# PMP20873E1_Power.net
KiCad netlist of a schematic drawn in Altium Designer
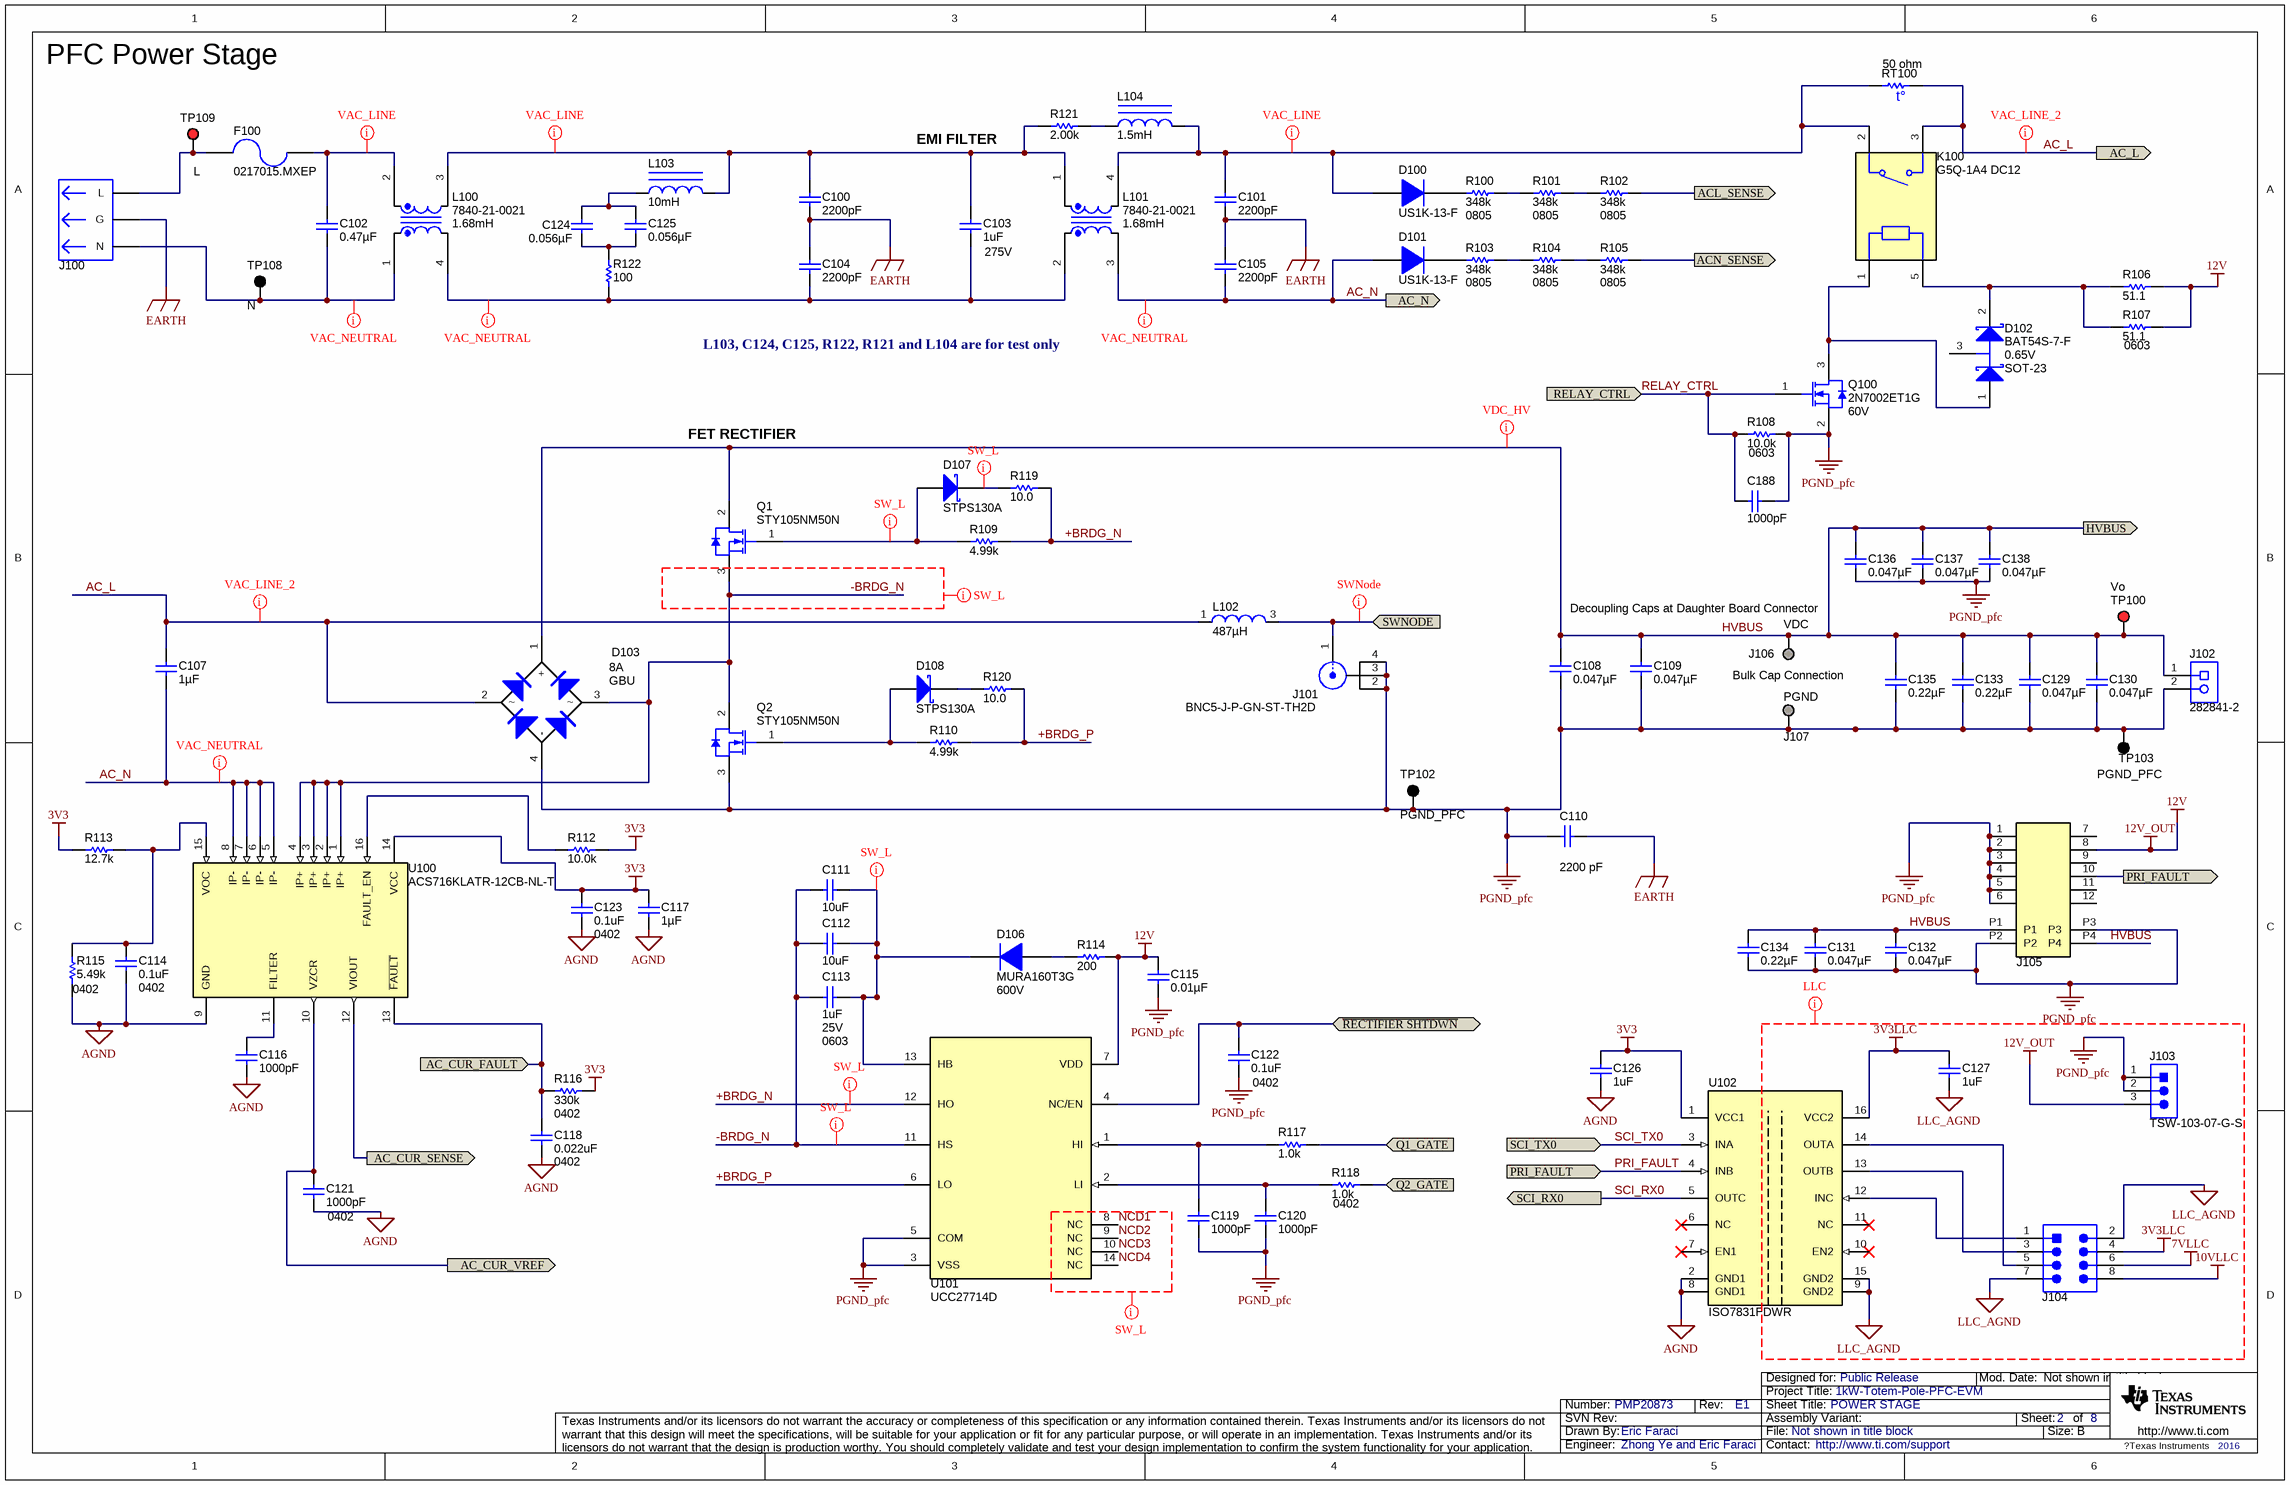
[diagram p0: PMP20873E1_Power.SchDoc]

(export (version "E")
  (design (tool "Eeschema 10.0.6"))
  (components
    (comp (ref "C100")
      (value "DE2E3KY222MA2BM01")
      (footprint "CAPRD500W60D800H850")
      (description "CAP, CERM, 2200pF, 250V, +/-20%, KY, Radial D8x5mm")
      (fields (field (name "VALUEDISPLAYED") "2200pF") (field (name "MANUFACTURER") "MuRata"))
      (libsource (lib "Capacitor_Ceramic") (part "DE2E3KY222MA2BM01"))
    )
    (comp (ref "C101")
      (value "DE2E3KY222MA2BM01")
      (footprint "CAPRD500W60D800H850")
      (description "CAP, CERM, 2200pF, 250V, +/-20%, KY, Radial D8x5mm")
      (fields (field (name "VALUEDISPLAYED") "2200pF") (field (name "MANUFACTURER") "MuRata"))
      (libsource (lib "Capacitor_Ceramic") (part "DE2E3KY222MA2BM01"))
    )
    (comp (ref "C102")
      (value "ECQ-U2A474ML")
      (footprint "CAPRR2250W80L2550T850H1750")
      (description "CAP, Film, 0.47 µF, 275 V, +/- 20%, TH")
      (fields (field (name "VALUEDISPLAYED") "0.47µF") (field (name "MANUFACTURER") "Panasonic"))
      (libsource (lib "Capacitor_Other") (part "ECQ-U2A474ML"))
    )
    (comp (ref "C103")
      (value "R46KN-4100--P1 M")
      (footprint "CAPRR2250W80L2550T850H1750")
      (description "CAP, Film, 1uF, 275V, +/-20%, TH")
      (fields
        (field (name "MANUFACTURER") "Panasonic")
        (field (name "VALUE2") "275V")
        (field (name "ALTERNATE PARTNUMBER") "R46KN410000P1M")
        (field (name "VALUEDISPLAYED") "1uF")
      )
      (libsource (lib "Capacitor_Other") (part "ECQ-U2A474ML"))
    )
    (comp (ref "C104")
      (value "DE2E3KY222MA2BM01")
      (footprint "CAPRD500W60D800H850")
      (description "CAP, CERM, 2200pF, 250V, +/-20%, KY, Radial D8x5mm")
      (fields (field (name "VALUEDISPLAYED") "2200pF") (field (name "MANUFACTURER") "MuRata"))
      (libsource (lib "Capacitor_Ceramic") (part "DE2E3KY222MA2BM01"))
    )
    (comp (ref "C105")
      (value "DE2E3KY222MA2BM01")
      (footprint "CAPRD500W60D800H850")
      (description "CAP, CERM, 2200pF, 250V, +/-20%, KY, Radial D8x5mm")
      (fields (field (name "VALUEDISPLAYED") "2200pF") (field (name "MANUFACTURER") "MuRata"))
      (libsource (lib "Capacitor_Ceramic") (part "DE2E3KY222MA2BM01"))
    )
    (comp (ref "C107")
      (value "450MPK105J")
      (footprint "MPK_1800x950")
      (description "CAP, Film, 1 µF, 450 V, +/- 5%, TH")
      (fields (field (name "VALUEDISPLAYED") "1µF") (field (name "MANUFACTURER") "Rubycon"))
      (libsource (lib "Capacitor_Other") (part "450MPK105J"))
    )
    (comp (ref "C108")
      (value "GRM32DR72J473KW01L")
      (footprint "1210")
      (description "CAP, CERM, 0.047 µF, 630 V, +/- 10%, X7R, 1210")
      (fields (field (name "VALUEDISPLAYED") "0.047µF") (field (name "MANUFACTURER") "MuRata"))
      (libsource (lib "Capacitor_Ceramic") (part "GRM32DR72J473KW01L"))
    )
    (comp (ref "C109")
      (value "GRM32DR72J473KW01L")
      (footprint "1210")
      (description "CAP, CERM, 0.047 µF, 630 V, +/- 10%, X7R, 1210")
      (fields (field (name "VALUEDISPLAYED") "0.047µF") (field (name "MANUFACTURER") "MuRata"))
      (libsource (lib "Capacitor_Ceramic") (part "GRM32DR72J473KW01L"))
    )
    (comp (ref "C110")
      (value "2200 pF")
      (footprint "CAPRD1000W60D900H1200")
      (description "CAP, CERM, 2200pF, 250V, +/-20%, E, Cap, 7x12x9 mm TH")
      (fields (field (name "MANUFACTURER") "Kemet") (field (name "PARTNUMBER") "C921U222MYWDBA7317"))
      (libsource (lib "Capacitor_Ceramic") (part "DE1E3KX222MA4BL01"))
    )
    (comp (ref "C111")
      (value "0805YD106MAT2A")
      (footprint "0805_HV")
      (description "CAP, CERM, 10uF, 16V, +/-20%, X5R, 0805")
      (fields (field (name "VALUEDISPLAYED") "10uF") (field (name "MANUFACTURER") "AVX"))
      (libsource (lib "Capacitor_Ceramic") (part "0805YD106MAT2A"))
    )
    (comp (ref "C112")
      (value "0805YD106MAT2A")
      (footprint "0805_HV")
      (description "CAP, CERM, 10uF, 16V, +/-20%, X5R, 0805")
      (fields (field (name "VALUEDISPLAYED") "10uF") (field (name "MANUFACTURER") "AVX"))
      (libsource (lib "Capacitor_Ceramic") (part "0805YD106MAT2A"))
    )
    (comp (ref "C113")
      (value "C1608X7R1E105K080AB")
      (footprint "0603")
      (description "CAP, CERM, 1uF, 25V, +/-10%, X7R, 0603")
      (fields
        (field (name "VALUEDISPLAYED") "1uF")
        (field (name "MANUFACTURER") "TDK")
        (field (name "VALUE2") "25V")
        (field (name "CAP_CASE") "0603")
      )
      (libsource (lib "Capacitor_Ceramic") (part "C1608X7R1E105K080AB"))
    )
    (comp (ref "C114")
      (value "GRM155R70J104KA01D")
      (footprint "0402")
      (description "CAP, CERM, 0.1uF, 6.3V, +/-10%, X7R, 0402")
      (fields
        (field (name "VALUEDISPLAYED") "0.1uF")
        (field (name "MANUFACTURER") "MuRata")
        (field (name "CAP_CASE") "0402")
      )
      (libsource (lib "Capacitor_Ceramic") (part "GRM155R70J104KA01D"))
    )
    (comp (ref "C115")
      (value "C0603X103K5RACTU")
      (footprint "0603")
      (description "CAP, CERM, 0.01uF, 50V, +/-10%, X7R, 0603")
      (fields (field (name "VALUEDISPLAYED") "0.01µF") (field (name "MANUFACTURER") "Kemet"))
      (libsource (lib "Capacitor_Ceramic") (part "C0603X103K5RACTU"))
    )
    (comp (ref "C116")
      (value "C1608X7R1H102K")
      (footprint "0603")
      (description "CAP, CERM, 1000pF, 50V, +/-10%, X7R, 0603")
      (fields (field (name "VALUEDISPLAYED") "1000pF") (field (name "MANUFACTURER") "TDK"))
      (libsource (lib "Capacitor_Ceramic") (part "C1608X7R1H102K"))
    )
    (comp (ref "C117")
      (value "GRM185R60J105KE26D")
      (footprint "0603")
      (description "CAP, CERM, 1uF, 6.3V, +/-10%, X5R, 0603")
      (fields (field (name "VALUEDISPLAYED") "1µF") (field (name "MANUFACTURER") "MuRata"))
      (libsource (lib "Capacitor_Ceramic") (part "GRM185R60J105KE26D"))
    )
    (comp (ref "C118")
      (value "GRM155R70J223KA01D")
      (footprint "0402")
      (description "CAP, CERM, 0.022uF, 6.3V, +/-10%, X7R, 0402")
      (fields
        (field (name "VALUEDISPLAYED") "0.022uF")
        (field (name "MANUFACTURER") "MuRata")
        (field (name "PACKAGEREFERENCE") "0402")
      )
      (libsource (lib "Capacitor_Ceramic") (part "GRM155R70J223KA01D"))
    )
    (comp (ref "C119")
      (value "C1005X7R1H102K")
      (footprint "0402")
      (description "CAP, CERM, 1000pF, 50V, +/-10%, X7R, 0402")
      (fields (field (name "VALUEDISPLAYED") "1000pF") (field (name "MANUFACTURER") "TDK"))
      (libsource (lib "Capacitor_Ceramic") (part "C1005X7R1H102K"))
    )
    (comp (ref "C120")
      (value "GRM155R60J102KA01D")
      (footprint "0402")
      (description "CAP, CERM, 1000pF, 6.3V, +/-10%, X5R, 0402")
      (fields (field (name "VALUEDISPLAYED") "1000pF") (field (name "MANUFACTURER") "MuRata"))
      (libsource (lib "Capacitor_Ceramic") (part "GRM155R60J102KA01D"))
    )
    (comp (ref "C121")
      (value "GRM155R60J102KA01D")
      (footprint "0402")
      (description "CAP, CERM, 1000pF, 6.3V, +/-10%, X5R, 0402")
      (fields
        (field (name "VALUEDISPLAYED") "1000pF")
        (field (name "MANUFACTURER") "MuRata")
        (field (name "PACKAGEREFERENCE") "0402")
      )
      (libsource (lib "Capacitor_Ceramic") (part "GRM155R60J102KA01D"))
    )
    (comp (ref "C122")
      (value "GRM155R70J104KA01D")
      (footprint "0402")
      (description "CAP, CERM, 0.1uF, 6.3V, +/-10%, X7R, 0402")
      (fields
        (field (name "VALUEDISPLAYED") "0.1uF")
        (field (name "MANUFACTURER") "MuRata")
        (field (name "PACKAGEREFERENCE") "0402")
      )
      (libsource (lib "Capacitor_Ceramic") (part "GRM155R70J104KA01D"))
    )
    (comp (ref "C123")
      (value "GRM155R70J104KA01D")
      (footprint "0402")
      (description "CAP, CERM, 0.1uF, 6.3V, +/-10%, X7R, 0402")
      (fields
        (field (name "VALUEDISPLAYED") "0.1uF")
        (field (name "MANUFACTURER") "MuRata")
        (field (name "CAP_CASE") "0402")
      )
      (libsource (lib "Capacitor_Ceramic") (part "GRM155R70J104KA01D"))
    )
    (comp (ref "C124")
      (value "GA355XR7GB563KW06L")
      (footprint "2220_330_N")
      (description "CAP, CERM, 0.056 µF, 250 V, +/- 10%, X7R, 2220")
      (fields (field (name "VALUEDISPLAYED") "0.056µF") (field (name "MANUFACTURER") "MuRata"))
      (libsource (lib "Capacitor_Ceramic") (part "GA355XR7GB563KW06L"))
    )
    (comp (ref "C125")
      (value "GA355XR7GB563KW06L")
      (footprint "2220_330_N")
      (description "CAP, CERM, 0.056 µF, 250 V, +/- 10%, X7R, 2220")
      (fields (field (name "VALUEDISPLAYED") "0.056µF") (field (name "MANUFACTURER") "MuRata"))
      (libsource (lib "Capacitor_Ceramic") (part "GA355XR7GB563KW06L"))
    )
    (comp (ref "C126")
      (value "C1608X7R1E105K080AB")
      (footprint "0603")
      (description "CAP, CERM, 1uF, 25V, +/-10%, X7R, 0603")
      (fields (field (name "VALUEDISPLAYED") "1uF") (field (name "MANUFACTURER") "TDK"))
      (libsource (lib "Capacitor_Ceramic") (part "C1608X7R1E105K080AB"))
    )
    (comp (ref "C127")
      (value "C1608X7R1E105K080AB")
      (footprint "0603")
      (description "CAP, CERM, 1uF, 25V, +/-10%, X7R, 0603")
      (fields (field (name "VALUEDISPLAYED") "1uF") (field (name "MANUFACTURER") "TDK"))
      (libsource (lib "Capacitor_Ceramic") (part "C1608X7R1E105K080AB"))
    )
    (comp (ref "C129")
      (value "GRM32DR72J473KW01L")
      (footprint "1210")
      (description "CAP, CERM, 0.047 µF, 630 V, +/- 10%, X7R, 1210")
      (fields (field (name "VALUEDISPLAYED") "0.047µF") (field (name "MANUFACTURER") "MuRata"))
      (libsource (lib "Capacitor_Ceramic") (part "GRM32DR72J473KW01L"))
    )
    (comp (ref "C130")
      (value "GRM32DR72J473KW01L")
      (footprint "1210")
      (description "CAP, CERM, 0.047 µF, 630 V, +/- 10%, X7R, 1210")
      (fields (field (name "VALUEDISPLAYED") "0.047µF") (field (name "MANUFACTURER") "MuRata"))
      (libsource (lib "Capacitor_Ceramic") (part "GRM32DR72J473KW01L"))
    )
    (comp (ref "C131")
      (value "GRM32DR72J473KW01L")
      (footprint "1210")
      (description "CAP, CERM, 0.047 µF, 630 V, +/- 10%, X7R, 1210")
      (fields (field (name "VALUEDISPLAYED") "0.047µF") (field (name "MANUFACTURER") "MuRata"))
      (libsource (lib "Capacitor_Ceramic") (part "GRM32DR72J473KW01L"))
    )
    (comp (ref "C132")
      (value "GRM32DR72J473KW01L")
      (footprint "1210")
      (description "CAP, CERM, 0.047 µF, 630 V, +/- 10%, X7R, 1210")
      (fields (field (name "VALUEDISPLAYED") "0.047µF") (field (name "MANUFACTURER") "MuRata"))
      (libsource (lib "Capacitor_Ceramic") (part "GRM32DR72J473KW01L"))
    )
    (comp (ref "C133")
      (value "GRM55DR72J224KW01L")
      (footprint "2220")
      (description "CAP, CERM, 0.22 µF, 630 V, +/- 10%, X7R, 2220")
      (fields (field (name "VALUEDISPLAYED") "0.22µF") (field (name "MANUFACTURER") "MuRata"))
      (libsource (lib "Capacitor_Ceramic") (part "GRM55DR72J224KW01L"))
    )
    (comp (ref "C134")
      (value "GRM55DR72J224KW01L")
      (footprint "2220")
      (description "CAP, CERM, 0.22 µF, 630 V, +/- 10%, X7R, 2220")
      (fields (field (name "VALUEDISPLAYED") "0.22µF") (field (name "MANUFACTURER") "MuRata"))
      (libsource (lib "Capacitor_Ceramic") (part "GRM55DR72J224KW01L"))
    )
    (comp (ref "C135")
      (value "GRM55DR72J224KW01L")
      (footprint "2220")
      (description "CAP, CERM, 0.22 µF, 630 V, +/- 10%, X7R, 2220")
      (fields (field (name "VALUEDISPLAYED") "0.22µF") (field (name "MANUFACTURER") "MuRata"))
      (libsource (lib "Capacitor_Ceramic") (part "GRM55DR72J224KW01L"))
    )
    (comp (ref "C136")
      (value "GRM32DR72J473KW01L")
      (footprint "1210")
      (description "CAP, CERM, 0.047 µF, 630 V, +/- 10%, X7R, 1210")
      (fields (field (name "VALUEDISPLAYED") "0.047µF") (field (name "MANUFACTURER") "MuRata"))
      (libsource (lib "Capacitor_Ceramic") (part "GRM32DR72J473KW01L"))
    )
    (comp (ref "C137")
      (value "GRM32DR72J473KW01L")
      (footprint "1210")
      (description "CAP, CERM, 0.047 µF, 630 V, +/- 10%, X7R, 1210")
      (fields (field (name "VALUEDISPLAYED") "0.047µF") (field (name "MANUFACTURER") "MuRata"))
      (libsource (lib "Capacitor_Ceramic") (part "GRM32DR72J473KW01L"))
    )
    (comp (ref "C138")
      (value "GRM32DR72J473KW01L")
      (footprint "1210")
      (description "CAP, CERM, 0.047 µF, 630 V, +/- 10%, X7R, 1210")
      (fields (field (name "VALUEDISPLAYED") "0.047µF") (field (name "MANUFACTURER") "MuRata"))
      (libsource (lib "Capacitor_Ceramic") (part "GRM32DR72J473KW01L"))
    )
    (comp (ref "C188")
      (value "GRM188R71C102KA01D")
      (footprint "0603")
      (description "CAP, CERM, 1000pF, 16V, +/-10%, X7R, 0603")
      (fields (field (name "VALUEDISPLAYED") "1000pF") (field (name "MANUFACTURER") "MuRata"))
      (libsource (lib "Capacitor_Ceramic") (part "GRM188R71C102KA01D"))
    )
    (comp (ref "D100")
      (value "US1K-13-F")
      (footprint "SMA")
      (description "Diode, Fast Rectifier, 800 V, 1 A, SMA")
      (fields (field (name "MANUFACTURER") "Diodes Inc."))
      (libsource (lib "Diode") (part "US1K-13-F"))
    )
    (comp (ref "D101")
      (value "US1K-13-F")
      (footprint "SMA")
      (description "Diode, Fast Rectifier, 800 V, 1 A, SMA")
      (fields (field (name "MANUFACTURER") "Diodes Inc."))
      (libsource (lib "Diode") (part "US1K-13-F"))
    )
    (comp (ref "D102")
      (value "BAT54S-7-F")
      (footprint "SOT-23")
      (description "Diode, Schottky, 30V, 0.2A, SOT-23")
      (fields
        (field (name "MANUFACTURER") "Diodes Inc.")
        (field (name "ALTIUM_VALUE") "0.65V")
        (field (name "PACKAGEREFERENCE") "SOT-23")
      )
      (libsource (lib "Diode") (part "BAT54S-7-F"))
    )
    (comp (ref "D103")
      (value "GBU8J-BP")
      (footprint "GBU")
      (description "Diode, Switching-Bridge, 420V, 8A, TH")
      (fields
        (field (name "MANUFACTURER") "Micro Commercial Components")
        (field (name "PACKAGEREFERENCE") "GBU")
        (field (name "VALUE1") "8A")
      )
      (libsource (lib "Diode") (part "GBU8J-BP"))
    )
    (comp (ref "D106")
      (value "MURA160T3G")
      (footprint "SMA")
      (description "Diode, Ultrafast, 600V, 1A, SMA")
      (fields (field (name "ALTIUM_VALUE") "600V") (field (name "MANUFACTURER") "ON Semiconductor"))
      (libsource (lib "Diode") (part "MURA160T3G"))
    )
    (comp (ref "D107")
      (value "STPS130A")
      (footprint "SMA")
      (description "Diode, Schottky, 30 V, 1 A, SMA")
      (fields (field (name "MANUFACTURER") "STMicroelectronics"))
      (libsource (lib "Diode") (part "STPS130A"))
    )
    (comp (ref "D108")
      (value "STPS130A")
      (footprint "SMA")
      (description "Diode, Schottky, 30 V, 1 A, SMA")
      (fields (field (name "MANUFACTURER") "STMicroelectronics"))
      (libsource (lib "Diode") (part "STPS130A"))
    )
    (comp (ref "F100")
      (value "0217015.MXEP")
      (footprint "Fuse_217_015_Verical")
      (description "Fuse, 15 A, 250 V, TH")
      (fields (field (name "MANUFACTURER") "Littelfuse"))
      (libsource (lib "Fuse") (part "0217015.MXEP"))
    )
    (comp (ref "J100")
      (value "703W-00/54")
      (footprint "CONN_QUALTEK-703W-0054")
      (description "AC Receptacle, 10A 250VAC")
      (fields (field (name "MANUFACTURER") "Qualtek Electronics Corporation"))
      (libsource (lib "Connectors_Other") (part "703W-00/54"))
    )
    (comp (ref "J101")
      (value "BNC5-J-P-GN-ST-TH2D")
      (footprint "Samtec_BNC5-J-P-GN-ST-TH2D")
      (description "50 OHM BNC ELEVATED STRAIGHT JACK, TH")
      (fields (field (name "MANUFACTURER") "Samtec"))
      (libsource (lib "Connectors_Samtec") (part "BNC5-J-P-GN-ST-TH2D"))
    )
    (comp (ref "J102")
      (value "282841-2")
      (footprint "TEC_282841-2")
      (description "Terminal Block, 2x1, 5.08mm, TH")
      (fields (field (name "MANUFACTURER") "TE Connectivity"))
      (libsource (lib "Connectors_TE_Connectivity") (part "282841-2"))
    )
    (comp (ref "J103")
      (value "TSW-103-07-G-S")
      (footprint "TSW-103-07-G-S")
      (description "Header, 100mil, 3x1, Gold, TH")
      (fields (field (name "MANUFACTURER") "Samtec"))
      (libsource (lib "Connectors_Samtec") (part "TSW-103-07-G-S"))
    )
    (comp (ref "J104")
      (value "TSW-104-07-G-D")
      (footprint "TSW-104-07-G-D")
      (description "Header, 100mil, 4x2, Gold, TH")
      (fields (field (name "MANUFACTURER") "Samtec"))
      (libsource (lib "Connectors_Samtec") (part "TSW-104-07-G-D"))
    )
    (comp (ref "J105")
      (value "PESC-02-12-02-01-L-RA-LC")
      (footprint "Samtec_PESC-02-12-02-01-x-RA-LC")
      (description "Signal Power Combo Socket Strip, 4x3, 4 Power Group, R/A, Gold, TH")
      (fields (field (name "MANUFACTURER") "Samtec"))
      (libsource (lib "Connectors_Samtec") (part "PESC-02-12-02-01-L-RA-LC"))
    )
    (comp (ref "J106")
      (value "VDC")
      (footprint "Mill-Max_0312-0-15-15-34-27-10-0")
      (description "Pin Receptacle, .032-.046\" .075\" Dia, Gold, TH")
      (fields (field (name "PARTNUMBER") "0312-0-15-15-34-27-10-0") (field (name "MANUFACTURER") "Mill-Max"))
      (libsource (lib "Connectors_Mill_Max") (part "0312-0-15-15-34-27-10-0"))
    )
    (comp (ref "J107")
      (value "PGND")
      (footprint "Mill-Max_0312-0-15-15-34-27-10-0")
      (description "Pin Receptacle, .032-.046\" .075\" Dia, Gold, TH")
      (fields (field (name "PARTNUMBER") "0312-0-15-15-34-27-10-0") (field (name "MANUFACTURER") "Mill-Max"))
      (libsource (lib "Connectors_Mill_Max") (part "0312-0-15-15-34-27-10-0"))
    )
    (comp (ref "K100")
      (value "G5Q-1A4 DC12")
      (footprint "Relay_G5Q-1A4")
      (description "Relay, SPST-NO (1 Form A), 10 A, 12 VDC, TH")
      (fields (field (name "MANUFACTURER") "Omron Electronic Components"))
      (libsource (lib "Relays") (part "G5Q-1A4 DC12"))
    )
    (comp (ref "L100")
      (value "7840-21-0021")
      (footprint "7840-21-0021")
      (description "Coupled inductor, 1.68 mH,  A,  ohm, TH")
      (fields (field (name "VALUEDISPLAYED") "1.68mH") (field (name "MANUFACTURER") "Nova Magnetics"))
      (libsource (lib "") (part "7840-21-0021_1"))
    )
    (comp (ref "L101")
      (value "7840-21-0021")
      (footprint "7840-21-0021")
      (description "Coupled inductor, 1.68 mH,  A,  ohm, TH")
      (fields (field (name "VALUEDISPLAYED") "1.68mH") (field (name "MANUFACTURER") "Nova Magnetics"))
      (libsource (lib "Coupled_Inductors") (part "7840-21-0021"))
    )
    (comp (ref "L102")
      (value "G164005LF")
      (footprint "IND_7840-09-0014")
      (description "Inductor, Toroid, Ferrite, 481 µH, 0.057 ohm, TH")
      (fields (field (name "VALUEDISPLAYED") "487µH") (field (name "MANUFACTURER") "GCI technologies"))
      (libsource (lib "Inductor_Other") (part "7840-09-0014"))
    )
    (comp (ref "L103")
      (value "ASPI-0403S-103M-T")
      (footprint "ASPI-0403S")
      (description "Inductor, Wirewound, 10 mH, 0.02 A, 32.8 ohm, SMD")
      (fields (field (name "VALUEDISPLAYED") "10mH") (field (name "MANUFACTURER") "Abracon Corporation"))
      (libsource (lib "Inductor_Other") (part "ASPI-0403S-103M-T"))
    )
    (comp (ref "L104")
      (value "LQH43MN152K03L")
      (footprint "LQH43M")
      (description "Inductor, Wirewound, Ferrite, 1.5 mH, 0.04 A, 37 ohm, SMD")
      (fields (field (name "VALUEDISPLAYED") "1.5mH") (field (name "MANUFACTURER") "MuRata"))
      (libsource (lib "Inductor_MuRata") (part "LQH43MN152K03L"))
    )
    (comp (ref "Q1")
      (value "STY105NM50N")
      (footprint "TO-247")
      (description "MOSFET, N-CH, 500 V, 110 A, TO-247")
      (fields (field (name "MANUFACTURER") "STMicroelectronics"))
      (libsource (lib "FETs") (part "STY105NM50N"))
    )
    (comp (ref "Q2")
      (value "STY105NM50N")
      (footprint "TO-247")
      (description "MOSFET, N-CH, 500 V, 110 A, TO-247")
      (fields (field (name "MANUFACTURER") "STMicroelectronics"))
      (libsource (lib "FETs") (part "STY105NM50N"))
    )
    (comp (ref "Q100")
      (value "2N7002ET1G")
      (footprint "SOT-23")
      (description "MOSFET, N-CH, 60V, 0.26A, SOT-23")
      (fields (field (name "MANUFACTURER") "ON Semiconductor") (field (name "ALTIUM_VALUE") "60V"))
      (libsource (lib "FETs") (part "2N7002ET1G"))
    )
    (comp (ref "R100")
      (value "348k")
      (footprint "0805_HV")
      (description "RES, 348k ohm, 0.1%, 0.125W, 0805")
      (fields
        (field (name "PARTNUMBER") "RT0805BRD07348KL")
        (field (name "MANUFACTURER") "Yageo America")
        (field (name "PACKAGEREFERENCE") "0805")
      )
      (libsource (lib "Resistor_0805") (part "RT0805BRD07348KL"))
    )
    (comp (ref "R101")
      (value "348k")
      (footprint "0805_HV")
      (description "RES, 348k ohm, 0.1%, 0.125W, 0805")
      (fields
        (field (name "PARTNUMBER") "RT0805BRD07348KL")
        (field (name "MANUFACTURER") "Yageo America")
        (field (name "PACKAGEREFERENCE") "0805")
      )
      (libsource (lib "Resistor_0805") (part "RT0805BRD07348KL"))
    )
    (comp (ref "R102")
      (value "348k")
      (footprint "0805_HV")
      (description "RES, 348k ohm, 0.1%, 0.125W, 0805")
      (fields
        (field (name "PARTNUMBER") "RT0805BRD07348KL")
        (field (name "MANUFACTURER") "Yageo America")
        (field (name "PACKAGEREFERENCE") "0805")
      )
      (libsource (lib "Resistor_0805") (part "RT0805BRD07348KL"))
    )
    (comp (ref "R103")
      (value "348k")
      (footprint "0805_HV")
      (description "RES, 348k ohm, 0.1%, 0.125W, 0805")
      (fields
        (field (name "PARTNUMBER") "RT0805BRD07348KL")
        (field (name "MANUFACTURER") "Yageo America")
        (field (name "PACKAGEREFERENCE") "0805")
      )
      (libsource (lib "Resistor_0805") (part "RT0805BRD07348KL"))
    )
    (comp (ref "R104")
      (value "348k")
      (footprint "0805_HV")
      (description "RES, 348k ohm, 0.1%, 0.125W, 0805")
      (fields
        (field (name "PARTNUMBER") "RT0805BRD07348KL")
        (field (name "MANUFACTURER") "Yageo America")
        (field (name "PACKAGEREFERENCE") "0805")
      )
      (libsource (lib "Resistor_0805") (part "RT0805BRD07348KL"))
    )
    (comp (ref "R105")
      (value "348k")
      (footprint "0805_HV")
      (description "RES, 348k ohm, 0.1%, 0.125W, 0805")
      (fields
        (field (name "PARTNUMBER") "RT0805BRD07348KL")
        (field (name "MANUFACTURER") "Yageo America")
        (field (name "PACKAGEREFERENCE") "0805")
      )
      (libsource (lib "Resistor_0805") (part "RT0805BRD07348KL"))
    )
    (comp (ref "R106")
      (value "51.1")
      (footprint "0603")
      (description "RES, 51.1 ohm, 1%, 0.1W, 0603")
      (fields (field (name "PARTNUMBER") "CRCW060351R1FKEA") (field (name "MANUFACTURER") "Vishay-Dale"))
      (libsource (lib "Resistor_0603") (part "CRCW060351R1FKEA"))
    )
    (comp (ref "R107")
      (value "51.1")
      (footprint "0603")
      (description "RES, 51.1 ohm, 1%, 0.1W, 0603")
      (fields
        (field (name "PARTNUMBER") "CRCW060351R1FKEA")
        (field (name "MANUFACTURER") "Vishay-Dale")
        (field (name "PACKAGEREFERENCE") "0603")
      )
      (libsource (lib "Resistor_0603") (part "CRCW060351R1FKEA"))
    )
    (comp (ref "R108")
      (value "10.0k")
      (footprint "0603")
      (description "RES, 10.0k ohm, 1%, 0.1W, 0603")
      (fields
        (field (name "PARTNUMBER") "RC0603FR-0710KL")
        (field (name "MANUFACTURER") "Yageo America")
        (field (name "PACKAGEREFERENCE") "0603")
      )
      (libsource (lib "Resistor_0603") (part "RC0603FR-0710KL"))
    )
    (comp (ref "R109")
      (value "ERJ-6ENF4991V")
      (footprint "0805_HV")
      (description "RES, 4.99 k, 1%, 0.125 W, 0805")
      (fields (field (name "VALUEDISPLAYED") "4.99k") (field (name "MANUFACTURER") "Panasonic"))
      (libsource (lib "Resistor_0805") (part "ERJ-6ENF4991V"))
    )
    (comp (ref "R110")
      (value "ERJ-6ENF4991V")
      (footprint "0805_HV")
      (description "RES, 4.99 k, 1%, 0.125 W, 0805")
      (fields (field (name "VALUEDISPLAYED") "4.99k") (field (name "MANUFACTURER") "Panasonic"))
      (libsource (lib "Resistor_0805") (part "ERJ-6ENF4991V"))
    )
    (comp (ref "R112")
      (value "10.0k")
      (footprint "0402")
      (description "RES, 10.0k ohm, 1%, 0.063W, 0402")
      (fields (field (name "PARTNUMBER") "CRCW040210K0FKED") (field (name "MANUFACTURER") "Vishay-Dale"))
      (libsource (lib "Resistor_0402") (part "CRCW040210K0FKED"))
    )
    (comp (ref "R113")
      (value "12.7k")
      (footprint "0402")
      (description "RES, 12.7k ohm, 1%, 0.063W, 0402")
      (fields (field (name "PARTNUMBER") "CRCW040212K7FKED") (field (name "MANUFACTURER") "Vishay-Dale"))
      (libsource (lib "Resistor_0402") (part "CRCW040212K7FKED"))
    )
    (comp (ref "R114")
      (value "200")
      (footprint "0603")
      (description "RES, 200 ohm, 1%, 0.1W, 0603")
      (fields (field (name "PARTNUMBER") "CRCW0603200RFKEA") (field (name "MANUFACTURER") "Vishay-Dale"))
      (libsource (lib "Resistor_0603") (part "CRCW0603200RFKEA"))
    )
    (comp (ref "R115")
      (value "5.49k")
      (footprint "0402")
      (description "RES, 5.49k ohm, 1%, 0.063W, 0402")
      (fields
        (field (name "PARTNUMBER") "CRCW04025K49FKED")
        (field (name "MANUFACTURER") "Vishay-Dale")
        (field (name "PACKAGEREFERENCE") "0402")
      )
      (libsource (lib "Resistor_0402") (part "CRCW04025K49FKED"))
    )
    (comp (ref "R116")
      (value "330k")
      (footprint "0402")
      (description "RES, 330k ohm, 5%, 0.063W, 0402")
      (fields
        (field (name "PARTNUMBER") "CRCW0402330KJNED")
        (field (name "MANUFACTURER") "Vishay-Dale")
        (field (name "PACKAGEREFERENCE") "0402")
      )
      (libsource (lib "Resistor_0402") (part "CRCW0402330KJNED"))
    )
    (comp (ref "R117")
      (value "1.0k")
      (footprint "0402")
      (description "RES, 1.0k ohm, 5%, 0.063W, 0402")
      (fields (field (name "PARTNUMBER") "CRCW04021K00JNED") (field (name "MANUFACTURER") "Vishay-Dale"))
      (libsource (lib "Resistor_0402") (part "CRCW04021K00JNED"))
    )
    (comp (ref "R118")
      (value "1.0k")
      (footprint "0402")
      (description "RES, 1.0k ohm, 5%, 0.063W, 0402")
      (fields
        (field (name "PARTNUMBER") "CRCW04021K00JNED")
        (field (name "MANUFACTURER") "Vishay-Dale")
        (field (name "PACKAGEREFERENCE") "0402")
      )
      (libsource (lib "Resistor_0402") (part "CRCW04021K00JNED"))
    )
    (comp (ref "R119")
      (value "CRCW080510R0FKEA")
      (footprint "0805_HV")
      (description "RES, 10.0, 1%, 0.125 W, 0805")
      (fields (field (name "VALUEDISPLAYED") "10.0") (field (name "MANUFACTURER") "Vishay-Dale"))
      (libsource (lib "Resistor_0805") (part "CRCW080510R0FKEA"))
    )
    (comp (ref "R120")
      (value "CRCW080510R0FKEA")
      (footprint "0805_HV")
      (description "RES, 10.0, 1%, 0.125 W, 0805")
      (fields (field (name "VALUEDISPLAYED") "10.0") (field (name "MANUFACTURER") "Vishay-Dale"))
      (libsource (lib "Resistor_0805") (part "CRCW080510R0FKEA"))
    )
    (comp (ref "R121")
      (value "CRCW12062K00FKEA")
      (footprint "1206")
      (description "RES, 2.00 k, 1%, 0.25 W, 1206")
      (fields (field (name "VALUEDISPLAYED") "2.00k") (field (name "MANUFACTURER") "Vishay-Dale"))
      (libsource (lib "Resistor_1206") (part "CRCW12062K00FKEA"))
    )
    (comp (ref "R122")
      (value "CRCW1206100RFKEA")
      (footprint "1206")
      (description "RES, 100, 1%, 0.25 W, 1206")
      (fields (field (name "VALUEDISPLAYED") "100") (field (name "MANUFACTURER") "Vishay-Dale"))
      (libsource (lib "Resistor_1206") (part "CRCW1206100RFKEA"))
    )
    (comp (ref "RT100")
      (value "50 ohm")
      (footprint "TDK_B751")
      (description "Thermistor NTC, 50 ohm, 25%, D12.5xH16.5mm")
      (fields (field (name "PARTNUMBER") "B59751B0120A070") (field (name "MANUFACTURER") "TDK"))
      (libsource (lib "ThermistorNTC") (part "B59751B0120A070"))
    )
    (comp (ref "TP100")
      (value "Vo")
      (footprint "Keystone5000")
      (description "Test Point, Miniature, Red, TH")
      (fields (field (name "PARTNUMBER") "5000") (field (name "MANUFACTURER") "Keystone"))
      (libsource (lib "Connectors_Keystone") (part "5000"))
    )
    (comp (ref "TP102")
      (value "PGND_PFC")
      (footprint "Keystone5001")
      (description "Test Point, Miniature, Black, TH")
      (fields (field (name "PARTNUMBER") "5001") (field (name "MANUFACTURER") "Keystone"))
      (libsource (lib "Connectors_Keystone") (part "5001"))
    )
    (comp (ref "TP103")
      (value "PGND_PFC")
      (footprint "Keystone5001")
      (description "Test Point, Miniature, Black, TH")
      (fields (field (name "PARTNUMBER") "5001") (field (name "MANUFACTURER") "Keystone"))
      (libsource (lib "Connectors_Keystone") (part "5001"))
    )
    (comp (ref "TP108")
      (value "N")
      (footprint "Keystone5001")
      (description "Test Point, Miniature, Black, TH")
      (fields (field (name "PARTNUMBER") "5001") (field (name "MANUFACTURER") "Keystone"))
      (libsource (lib "Connectors_Keystone") (part "5001"))
    )
    (comp (ref "TP109")
      (value "L")
      (footprint "Keystone5000")
      (description "Test Point, Miniature, Red, TH")
      (fields (field (name "PARTNUMBER") "5000") (field (name "MANUFACTURER") "Keystone"))
      (libsource (lib "Connectors_Keystone") (part "5000"))
    )
    (comp (ref "U100")
      (value "ACS716KLATR-12CB-NL-T")
      (footprint "SOIC-16")
      (description "120 kHz Bandwidth, High-Voltage Isolation Current Sensor with Integrated Overcurrent Detection")
      (fields (field (name "MANUFACTURER") "Allegro Microsystems Inc"))
      (libsource (lib "Other_IC") (part "ACS716KLATR-12CB-NL-T"))
    )
    (comp (ref "U101")
      (value "UCC27714D")
      (footprint "D0014A_N")
      (description "High-Speed,4A, 600V High-side Low-side Gate Driver Device, D0014A")
      (fields (field (name "MANUFACTURER") "Texas Instruments"))
      (libsource (lib "TI_Pre_RTM") (part "UCC27714D"))
    )
    (comp (ref "U102")
      (value "ISO7831FDWR")
      (footprint "DW0016B_N")
      (description "High-Performance, 8000 VPK Reinforced Triple Digital Isolator, DW0016B")
      (fields
        (field (name "ALTERNATE PARTNUMBER") "ISO7831FDW")
        (field (name "MANUFACTURER") "Texas Instruments")
      )
      (libsource (lib "TI_Pre_Release1") (part "ISO7831FDWR"))
    )
  )
  (nets
    (net (code "1") (name "/+BRDG_N") (class "Default")
      (node (ref "R109") (pin "2") (pinfunction "2_2") (pintype "passive"))
      (node (ref "R119") (pin "2") (pinfunction "2_2") (pintype "passive"))
      (node (ref "U101") (pin "12") (pinfunction "HO_12") (pintype "power_in"))
    )
    (net (code "2") (name "/+BRDG_P") (class "Default")
      (node (ref "R110") (pin "2") (pinfunction "2_2") (pintype "passive"))
      (node (ref "R120") (pin "2") (pinfunction "2_2") (pintype "passive"))
      (node (ref "U101") (pin "6") (pinfunction "LO_6") (pintype "power_in"))
    )
    (net (code "3") (name "/-BRDG_N") (class "Default")
      (node (ref "C111") (pin "2") (pinfunction "2_2") (pintype "passive"))
      (node (ref "C112") (pin "2") (pinfunction "2_2") (pintype "passive"))
      (node (ref "C113") (pin "1") (pinfunction "1_1") (pintype "passive"))
      (node (ref "D103") (pin "3") (pinfunction "~_3") (pintype "passive"))
      (node (ref "Q1") (pin "3") (pinfunction "S_3") (pintype "passive"))
      (node (ref "Q2") (pin "2") (pinfunction "D_2") (pintype "passive"))
      (node (ref "U100") (pin "1") (pinfunction "IP+_1") (pintype "input"))
      (node (ref "U100") (pin "2") (pinfunction "IP+_2") (pintype "input"))
      (node (ref "U100") (pin "3") (pinfunction "IP+_3") (pintype "input"))
      (node (ref "U100") (pin "4") (pinfunction "IP+_4") (pintype "input"))
      (node (ref "U101") (pin "11") (pinfunction "HS_11") (pintype "power_in"))
    )
    (net (code "4") (name "/ACL_SENSE") (class "Default")
      (node (ref "R102") (pin "1") (pinfunction "1_1") (pintype "passive"))
    )
    (net (code "5") (name "/ACN_SENSE") (class "Default")
      (node (ref "R105") (pin "1") (pinfunction "1_1") (pintype "passive"))
    )
    (net (code "6") (name "/AC_CUR_FAULT") (class "Default")
      (node (ref "C118") (pin "2") (pinfunction "2_2") (pintype "passive"))
      (node (ref "R116") (pin "2") (pinfunction "2_2") (pintype "passive"))
      (node (ref "U100") (pin "13") (pinfunction "~{FAULT}_13") (pintype "open_collector"))
    )
    (net (code "7") (name "/AC_CUR_SENSE") (class "Default")
      (node (ref "U100") (pin "12") (pinfunction "VIOUT_12") (pintype "output"))
    )
    (net (code "8") (name "/AC_CUR_VREF") (class "Default")
      (node (ref "C121") (pin "1") (pinfunction "1_1") (pintype "passive"))
      (node (ref "U100") (pin "10") (pinfunction "VZCR_10") (pintype "output"))
    )
    (net (code "9") (name "/AC_L") (class "Default")
      (node (ref "C107") (pin "1") (pinfunction "1_1") (pintype "passive"))
      (node (ref "D103") (pin "2") (pinfunction "~_2") (pintype "passive"))
      (node (ref "K100") (pin "3") (pinfunction "3_3") (pintype "passive"))
      (node (ref "L102") (pin "1") (pinfunction "1_1") (pintype "passive"))
      (node (ref "RT100") (pin "2") (pinfunction "2_2") (pintype "passive"))
    )
    (net (code "10") (name "/AC_N") (class "Default")
      (node (ref "C105") (pin "2") (pinfunction "2_2") (pintype "passive"))
      (node (ref "C107") (pin "2") (pinfunction "2_2") (pintype "passive"))
      (node (ref "D101") (pin "2") (pinfunction "A_2") (pintype "passive"))
      (node (ref "L101") (pin "3") (pinfunction "3_3") (pintype "passive"))
      (node (ref "U100") (pin "5") (pinfunction "IP-_5") (pintype "input"))
      (node (ref "U100") (pin "6") (pinfunction "IP-_6") (pintype "input"))
      (node (ref "U100") (pin "7") (pinfunction "IP-_7") (pintype "input"))
      (node (ref "U100") (pin "8") (pinfunction "IP-_8") (pintype "input"))
    )
    (net (code "11") (name "/HVBUS") (class "Default")
      (node (ref "C108") (pin "1") (pinfunction "1_1") (pintype "passive"))
      (node (ref "C109") (pin "1") (pinfunction "1_1") (pintype "passive"))
      (node (ref "C129") (pin "1") (pinfunction "1_1") (pintype "passive"))
      (node (ref "C130") (pin "1") (pinfunction "1_1") (pintype "passive"))
      (node (ref "C131") (pin "1") (pinfunction "1_1") (pintype "passive"))
      (node (ref "C132") (pin "1") (pinfunction "1_1") (pintype "passive"))
      (node (ref "C133") (pin "2") (pinfunction "2_2") (pintype "passive"))
      (node (ref "C134") (pin "1") (pinfunction "1_1") (pintype "passive"))
      (node (ref "C135") (pin "2") (pinfunction "2_2") (pintype "passive"))
      (node (ref "C136") (pin "1") (pinfunction "1_1") (pintype "passive"))
      (node (ref "C137") (pin "1") (pinfunction "1_1") (pintype "passive"))
      (node (ref "C138") (pin "1") (pinfunction "1_1") (pintype "passive"))
      (node (ref "D103") (pin "1") (pinfunction "+_1") (pintype "passive"))
      (node (ref "J102") (pin "1") (pinfunction "1_1") (pintype "passive"))
      (node (ref "J105") (pin "P1") (pinfunction "P1_P1") (pintype "passive"))
      (node (ref "J105") (pin "P4") (pinfunction "P4_P4") (pintype "passive"))
      (node (ref "J106") (pin "1") (pintype "passive"))
      (node (ref "Q1") (pin "2") (pinfunction "D_2") (pintype "passive"))
      (node (ref "TP100") (pin "1") (pintype "passive"))
    )
    (net (code "12") (name "/NCD1") (class "Default")
      (node (ref "U101") (pin "8") (pinfunction "NC_8") (pintype "passive"))
    )
    (net (code "13") (name "/NCD2") (class "Default")
      (node (ref "U101") (pin "9") (pinfunction "NC_9") (pintype "passive"))
    )
    (net (code "14") (name "/NCD3") (class "Default")
      (node (ref "U101") (pin "10") (pinfunction "NC_10") (pintype "passive"))
    )
    (net (code "15") (name "/NCD4") (class "Default")
      (node (ref "U101") (pin "14") (pinfunction "NC_14") (pintype "passive"))
    )
    (net (code "16") (name "/PRI_FAULT") (class "Default")
      (node (ref "J105") (pin "10") (pinfunction "10_10") (pintype "passive"))
      (node (ref "U102") (pin "4") (pinfunction "INB_4") (pintype "input"))
    )
    (net (code "17") (name "/Q1_GATE") (class "Default")
      (node (ref "R117") (pin "2") (pinfunction "2_2") (pintype "passive"))
    )
    (net (code "18") (name "/Q2_GATE") (class "Default")
      (node (ref "R118") (pin "2") (pinfunction "2_2") (pintype "passive"))
    )
    (net (code "19") (name "/RECTIFIER SHTDWN") (class "Default")
      (node (ref "C122") (pin "1") (pinfunction "1_1") (pintype "passive"))
      (node (ref "U101") (pin "4") (pinfunction "NC/EN_4") (pintype "passive"))
    )
    (net (code "20") (name "/RELAY_CTRL") (class "Default")
      (node (ref "C188") (pin "2") (pinfunction "2_2") (pintype "passive"))
      (node (ref "Q100") (pin "1") (pinfunction "G_1") (pintype "passive"))
      (node (ref "R108") (pin "1") (pinfunction "1_1") (pintype "passive"))
    )
    (net (code "21") (name "/SCI_RX0") (class "Default")
      (node (ref "U102") (pin "5") (pinfunction "OUTC_5") (pintype "tri_state"))
    )
    (net (code "22") (name "/SCI_TX0") (class "Default")
      (node (ref "U102") (pin "3") (pinfunction "INA_3") (pintype "input"))
    )
    (net (code "23") (name "/SWNODE") (class "Default")
      (node (ref "J101") (pin "1") (pinfunction "1_1") (pintype "passive"))
      (node (ref "L102") (pin "3") (pinfunction "3_3") (pintype "passive"))
    )
    (net (code "24") (name "3V3") (class "Default")
      (node (ref "C117") (pin "1") (pinfunction "1_1") (pintype "passive"))
      (node (ref "C123") (pin "1") (pinfunction "1_1") (pintype "passive"))
      (node (ref "C126") (pin "2") (pinfunction "2_2") (pintype "passive"))
      (node (ref "R112") (pin "2") (pinfunction "2_2") (pintype "passive"))
      (node (ref "R113") (pin "2") (pinfunction "2_2") (pintype "passive"))
      (node (ref "R116") (pin "1") (pinfunction "1_1") (pintype "passive"))
      (node (ref "U100") (pin "14") (pinfunction "VCC_14") (pintype "power_in"))
      (node (ref "U102") (pin "1") (pinfunction "VCC1_1") (pintype "power_in"))
    )
    (net (code "25") (name "3V3LLC") (class "Default")
      (node (ref "C127") (pin "2") (pinfunction "2_2") (pintype "passive"))
      (node (ref "J104") (pin "4") (pinfunction "4_4") (pintype "passive"))
      (node (ref "U102") (pin "16") (pinfunction "VCC2_16") (pintype "power_in"))
    )
    (net (code "26") (name "7VLLC") (class "Default")
      (node (ref "J104") (pin "6") (pinfunction "6_6") (pintype "passive"))
    )
    (net (code "27") (name "10VLLC") (class "Default")
      (node (ref "J104") (pin "8") (pinfunction "8_8") (pintype "passive"))
    )
    (net (code "28") (name "12V") (class "Default")
      (node (ref "C115") (pin "1") (pinfunction "1_1") (pintype "passive"))
      (node (ref "J103") (pin "3") (pinfunction "3_3") (pintype "passive"))
      (node (ref "J105") (pin "8") (pinfunction "8_8") (pintype "passive"))
      (node (ref "R106") (pin "2") (pinfunction "2_2") (pintype "passive"))
      (node (ref "R107") (pin "2") (pinfunction "2_2") (pintype "passive"))
      (node (ref "R114") (pin "2") (pinfunction "2_2") (pintype "passive"))
      (node (ref "U101") (pin "7") (pinfunction "VDD_7") (pintype "power_in"))
    )
    (net (code "29") (name "AGND") (class "Default")
      (node (ref "C114") (pin "2") (pinfunction "2_2") (pintype "passive"))
      (node (ref "C116") (pin "2") (pinfunction "2_2") (pintype "passive"))
      (node (ref "C117") (pin "2") (pinfunction "2_2") (pintype "passive"))
      (node (ref "C118") (pin "1") (pinfunction "1_1") (pintype "passive"))
      (node (ref "C121") (pin "2") (pinfunction "2_2") (pintype "passive"))
      (node (ref "C123") (pin "2") (pinfunction "2_2") (pintype "passive"))
      (node (ref "C126") (pin "1") (pinfunction "1_1") (pintype "passive"))
      (node (ref "R115") (pin "1") (pinfunction "1_1") (pintype "passive"))
      (node (ref "U100") (pin "9") (pinfunction "GND_9") (pintype "power_in"))
      (node (ref "U102") (pin "2") (pinfunction "GND1_2") (pintype "power_in"))
      (node (ref "U102") (pin "8") (pinfunction "GND1_8") (pintype "power_in"))
    )
    (net (code "30") (name "EARTH") (class "Default")
      (node (ref "C100") (pin "2") (pinfunction "2_2") (pintype "passive"))
      (node (ref "C101") (pin "2") (pinfunction "2_2") (pintype "passive"))
      (node (ref "C104") (pin "1") (pinfunction "1_1") (pintype "passive"))
      (node (ref "C105") (pin "1") (pinfunction "1_1") (pintype "passive"))
      (node (ref "C110") (pin "1") (pinfunction "1_1") (pintype "passive"))
      (node (ref "J100") (pin "3") (pinfunction "G_3") (pintype "passive"))
    )
    (net (code "31") (name "LLC_AGND") (class "Default")
      (node (ref "C127") (pin "1") (pinfunction "1_1") (pintype "passive"))
      (node (ref "J104") (pin "2") (pinfunction "2_2") (pintype "passive"))
      (node (ref "J104") (pin "7") (pinfunction "7_7") (pintype "passive"))
      (node (ref "U102") (pin "15") (pinfunction "GND2_15") (pintype "power_in"))
      (node (ref "U102") (pin "9") (pinfunction "GND2_9") (pintype "power_in"))
    )
    (net (code "32") (name "Net-(C100-Pad1)") (class "Default")
      (node (ref "C100") (pin "1") (pinfunction "1_1") (pintype "passive"))
      (node (ref "C103") (pin "1") (pinfunction "1_1") (pintype "passive"))
      (node (ref "L100") (pin "3") (pinfunction "3_3") (pintype "passive"))
      (node (ref "L101") (pin "1") (pinfunction "1_1") (pintype "passive"))
      (node (ref "L103") (pin "2") (pinfunction "2_2") (pintype "passive"))
      (node (ref "R121") (pin "1") (pinfunction "1_1") (pintype "passive"))
    )
    (net (code "33") (name "Net-(C102-Pad1)") (class "Default")
      (node (ref "C102") (pin "1") (pinfunction "1_1") (pintype "passive"))
      (node (ref "F100") (pin "2") (pinfunction "2_2") (pintype "passive"))
      (node (ref "L100") (pin "2") (pinfunction "2_2") (pintype "passive"))
    )
    (net (code "34") (name "Net-(C103-Pad2)") (class "Default")
      (node (ref "C103") (pin "2") (pinfunction "2_2") (pintype "passive"))
      (node (ref "C104") (pin "2") (pinfunction "2_2") (pintype "passive"))
      (node (ref "L100") (pin "4") (pinfunction "4_4") (pintype "passive"))
      (node (ref "L101") (pin "2") (pinfunction "2_2") (pintype "passive"))
      (node (ref "R122") (pin "1") (pinfunction "1_1") (pintype "passive"))
    )
    (net (code "35") (name "Net-(C124-Pad1)") (class "Default")
      (node (ref "C124") (pin "1") (pinfunction "1_1") (pintype "passive"))
      (node (ref "C125") (pin "1") (pinfunction "1_1") (pintype "passive"))
      (node (ref "L103") (pin "1") (pinfunction "1_1") (pintype "passive"))
    )
    (net (code "36") (name "Net-(C124-Pad2)") (class "Default")
      (node (ref "C124") (pin "2") (pinfunction "2_2") (pintype "passive"))
      (node (ref "C125") (pin "2") (pinfunction "2_2") (pintype "passive"))
      (node (ref "R122") (pin "2") (pinfunction "2_2") (pintype "passive"))
    )
    (net (code "37") (name "Net-(D100-A)") (class "Default")
      (node (ref "C101") (pin "1") (pinfunction "1_1") (pintype "passive"))
      (node (ref "D100") (pin "2") (pinfunction "A_2") (pintype "passive"))
      (node (ref "K100") (pin "2") (pinfunction "2_2") (pintype "passive"))
      (node (ref "L101") (pin "4") (pinfunction "4_4") (pintype "passive"))
      (node (ref "L104") (pin "2") (pinfunction "2_2") (pintype "passive"))
      (node (ref "RT100") (pin "1") (pinfunction "1_1") (pintype "passive"))
    )
    (net (code "38") (name "Net-(D100-K)") (class "Default")
      (node (ref "D100") (pin "1") (pinfunction "K_1") (pintype "passive"))
      (node (ref "R100") (pin "2") (pinfunction "2_2") (pintype "passive"))
    )
    (net (code "39") (name "Net-(D101-K)") (class "Default")
      (node (ref "D101") (pin "1") (pinfunction "K_1") (pintype "passive"))
      (node (ref "R103") (pin "2") (pinfunction "2_2") (pintype "passive"))
    )
    (net (code "40") (name "Net-(D102-A)") (class "Default")
      (node (ref "D102") (pin "1") (pinfunction "A_1") (pintype "passive"))
      (node (ref "K100") (pin "1") (pinfunction "1_1") (pintype "passive"))
      (node (ref "Q100") (pin "3") (pinfunction "D_3") (pintype "passive"))
    )
    (net (code "41") (name "Net-(D102-K)") (class "Default")
      (node (ref "D102") (pin "2") (pinfunction "K_2") (pintype "passive"))
      (node (ref "K100") (pin "5") (pinfunction "5_5") (pintype "passive"))
      (node (ref "R106") (pin "1") (pinfunction "1_1") (pintype "passive"))
      (node (ref "R107") (pin "1") (pinfunction "1_1") (pintype "passive"))
    )
    (net (code "42") (name "Net-(D106-A)") (class "Default")
      (node (ref "D106") (pin "2") (pinfunction "A_2") (pintype "passive"))
      (node (ref "R114") (pin "1") (pinfunction "1_1") (pintype "passive"))
    )
    (net (code "43") (name "Net-(D106-K)") (class "Default")
      (node (ref "C111") (pin "1") (pinfunction "1_1") (pintype "passive"))
      (node (ref "C112") (pin "1") (pinfunction "1_1") (pintype "passive"))
      (node (ref "C113") (pin "2") (pinfunction "2_2") (pintype "passive"))
      (node (ref "D106") (pin "1") (pinfunction "K_1") (pintype "passive"))
      (node (ref "U101") (pin "13") (pinfunction "HB_13") (pintype "power_in"))
    )
    (net (code "44") (name "Net-(D107-A)") (class "Default")
      (node (ref "D107") (pin "2") (pinfunction "A_2") (pintype "passive"))
      (node (ref "Q1") (pin "1") (pinfunction "G_1") (pintype "passive"))
      (node (ref "R109") (pin "1") (pinfunction "1_1") (pintype "passive"))
    )
    (net (code "45") (name "Net-(D107-K)") (class "Default")
      (node (ref "D107") (pin "1") (pinfunction "K_1") (pintype "passive"))
      (node (ref "R119") (pin "1") (pinfunction "1_1") (pintype "passive"))
    )
    (net (code "46") (name "Net-(D108-A)") (class "Default")
      (node (ref "D108") (pin "2") (pinfunction "A_2") (pintype "passive"))
      (node (ref "Q2") (pin "1") (pinfunction "G_1") (pintype "passive"))
      (node (ref "R110") (pin "1") (pinfunction "1_1") (pintype "passive"))
    )
    (net (code "47") (name "Net-(D108-K)") (class "Default")
      (node (ref "D108") (pin "1") (pinfunction "K_1") (pintype "passive"))
      (node (ref "R120") (pin "1") (pinfunction "1_1") (pintype "passive"))
    )
    (net (code "48") (name "Net-(J100-L)") (class "Default")
      (node (ref "F100") (pin "1") (pinfunction "1_1") (pintype "passive"))
      (node (ref "J100") (pin "1") (pinfunction "L_1") (pintype "passive"))
      (node (ref "TP109") (pin "1") (pintype "passive"))
    )
    (net (code "49") (name "Net-(J100-N)") (class "Default")
      (node (ref "C102") (pin "2") (pinfunction "2_2") (pintype "passive"))
      (node (ref "J100") (pin "2") (pinfunction "N_2") (pintype "passive"))
      (node (ref "L100") (pin "1") (pinfunction "1_1") (pintype "passive"))
      (node (ref "TP108") (pin "1") (pintype "passive"))
    )
    (net (code "50") (name "Net-(L104-Pad1)") (class "Default")
      (node (ref "L104") (pin "1") (pinfunction "1_1") (pintype "passive"))
      (node (ref "R121") (pin "2") (pinfunction "2_2") (pintype "passive"))
    )
    (net (code "51") (name "Net-(R100-Pad1)") (class "Default")
      (node (ref "R100") (pin "1") (pinfunction "1_1") (pintype "passive"))
      (node (ref "R101") (pin "2") (pinfunction "2_2") (pintype "passive"))
    )
    (net (code "52") (name "Net-(R101-Pad1)") (class "Default")
      (node (ref "R101") (pin "1") (pinfunction "1_1") (pintype "passive"))
      (node (ref "R102") (pin "2") (pinfunction "2_2") (pintype "passive"))
    )
    (net (code "53") (name "Net-(R103-Pad1)") (class "Default")
      (node (ref "R103") (pin "1") (pinfunction "1_1") (pintype "passive"))
      (node (ref "R104") (pin "2") (pinfunction "2_2") (pintype "passive"))
    )
    (net (code "54") (name "Net-(R104-Pad1)") (class "Default")
      (node (ref "R104") (pin "1") (pinfunction "1_1") (pintype "passive"))
      (node (ref "R105") (pin "2") (pinfunction "2_2") (pintype "passive"))
    )
    (net (code "55") (name "Net-(U100-FAULT_EN)") (class "Default")
      (node (ref "R112") (pin "1") (pinfunction "1_1") (pintype "passive"))
      (node (ref "U100") (pin "16") (pinfunction "FAULT_EN_16") (pintype "input"))
    )
    (net (code "56") (name "Net-(U100-FILTER)") (class "Default")
      (node (ref "C116") (pin "1") (pinfunction "1_1") (pintype "passive"))
      (node (ref "U100") (pin "11") (pinfunction "FILTER_11") (pintype "passive"))
    )
    (net (code "57") (name "Net-(U100-VOC)") (class "Default")
      (node (ref "C114") (pin "1") (pinfunction "1_1") (pintype "passive"))
      (node (ref "R113") (pin "1") (pinfunction "1_1") (pintype "passive"))
      (node (ref "R115") (pin "2") (pinfunction "2_2") (pintype "passive"))
      (node (ref "U100") (pin "15") (pinfunction "VOC_15") (pintype "input"))
    )
    (net (code "58") (name "Net-(U101-HI)") (class "Default")
      (node (ref "C119") (pin "1") (pinfunction "1_1") (pintype "passive"))
      (node (ref "R117") (pin "1") (pinfunction "1_1") (pintype "passive"))
      (node (ref "U101") (pin "1") (pinfunction "HI_1") (pintype "input"))
    )
    (net (code "59") (name "Net-(U101-LI)") (class "Default")
      (node (ref "C120") (pin "1") (pinfunction "1_1") (pintype "passive"))
      (node (ref "R118") (pin "1") (pinfunction "1_1") (pintype "passive"))
      (node (ref "U101") (pin "2") (pinfunction "LI_2") (pintype "input"))
    )
    (net (code "60") (name "Net-(U102-INC)") (class "Default")
      (node (ref "J104") (pin "1") (pinfunction "1_1") (pintype "passive"))
      (node (ref "U102") (pin "12") (pinfunction "INC_12") (pintype "input"))
    )
    (net (code "61") (name "Net-(U102-OUTA)") (class "Default")
      (node (ref "J104") (pin "5") (pinfunction "5_5") (pintype "passive"))
      (node (ref "U102") (pin "14") (pinfunction "OUTA_14") (pintype "tri_state"))
    )
    (net (code "62") (name "Net-(U102-OUTB)") (class "Default")
      (node (ref "J104") (pin "3") (pinfunction "3_3") (pintype "passive"))
      (node (ref "U102") (pin "13") (pinfunction "OUTB_13") (pintype "tri_state"))
    )
    (net (code "63") (name "PGND_pfc") (class "Default")
      (node (ref "C108") (pin "2") (pinfunction "2_2") (pintype "passive"))
      (node (ref "C109") (pin "2") (pinfunction "2_2") (pintype "passive"))
      (node (ref "C110") (pin "2") (pinfunction "2_2") (pintype "passive"))
      (node (ref "C115") (pin "2") (pinfunction "2_2") (pintype "passive"))
      (node (ref "C119") (pin "2") (pinfunction "2_2") (pintype "passive"))
      (node (ref "C120") (pin "2") (pinfunction "2_2") (pintype "passive"))
      (node (ref "C122") (pin "2") (pinfunction "2_2") (pintype "passive"))
      (node (ref "C129") (pin "2") (pinfunction "2_2") (pintype "passive"))
      (node (ref "C130") (pin "2") (pinfunction "2_2") (pintype "passive"))
      (node (ref "C131") (pin "2") (pinfunction "2_2") (pintype "passive"))
      (node (ref "C132") (pin "2") (pinfunction "2_2") (pintype "passive"))
      (node (ref "C133") (pin "1") (pinfunction "1_1") (pintype "passive"))
      (node (ref "C134") (pin "2") (pinfunction "2_2") (pintype "passive"))
      (node (ref "C135") (pin "1") (pinfunction "1_1") (pintype "passive"))
      (node (ref "C136") (pin "2") (pinfunction "2_2") (pintype "passive"))
      (node (ref "C137") (pin "2") (pinfunction "2_2") (pintype "passive"))
      (node (ref "C138") (pin "2") (pinfunction "2_2") (pintype "passive"))
      (node (ref "C188") (pin "1") (pinfunction "1_1") (pintype "passive"))
      (node (ref "D103") (pin "4") (pinfunction "-_4") (pintype "passive"))
      (node (ref "J101") (pin "2") (pinfunction "2_2") (pintype "passive"))
      (node (ref "J101") (pin "3") (pinfunction "3_3") (pintype "passive"))
      (node (ref "J101") (pin "4") (pinfunction "4_4") (pintype "passive"))
      (node (ref "J102") (pin "2") (pinfunction "2_2") (pintype "passive"))
      (node (ref "J103") (pin "1") (pinfunction "1_1") (pintype "passive"))
      (node (ref "J103") (pin "2") (pinfunction "2_2") (pintype "passive"))
      (node (ref "J105") (pin "1") (pinfunction "1_1") (pintype "passive"))
      (node (ref "J105") (pin "2") (pinfunction "2_2") (pintype "passive"))
      (node (ref "J105") (pin "3") (pinfunction "3_3") (pintype "passive"))
      (node (ref "J105") (pin "4") (pinfunction "4_4") (pintype "passive"))
      (node (ref "J105") (pin "5") (pinfunction "5_5") (pintype "passive"))
      (node (ref "J105") (pin "6") (pinfunction "6_6") (pintype "passive"))
      (node (ref "J105") (pin "P2") (pinfunction "P2_P2") (pintype "passive"))
      (node (ref "J105") (pin "P3") (pinfunction "P3_P3") (pintype "passive"))
      (node (ref "J107") (pin "1") (pintype "passive"))
      (node (ref "Q100") (pin "2") (pinfunction "S_2") (pintype "passive"))
      (node (ref "Q2") (pin "3") (pinfunction "S_3") (pintype "passive"))
      (node (ref "R108") (pin "2") (pinfunction "2_2") (pintype "passive"))
      (node (ref "TP102") (pin "1") (pintype "passive"))
      (node (ref "TP103") (pin "1") (pintype "passive"))
      (node (ref "U101") (pin "3") (pinfunction "VSS_3") (pintype "power_in"))
      (node (ref "U101") (pin "5") (pinfunction "COM_5") (pintype "power_in"))
    )
    (net (code "64") (name "unconnected-(D102-C-Pad3)") (class "Default")
      (node (ref "D102") (pin "3") (pinfunction "C_3") (pintype "passive"))
    )
    (net (code "65") (name "unconnected-(J105-Pad7)") (class "Default")
      (node (ref "J105") (pin "7") (pinfunction "7_7") (pintype "passive"))
    )
    (net (code "66") (name "unconnected-(J105-Pad9)") (class "Default")
      (node (ref "J105") (pin "9") (pinfunction "9_9") (pintype "passive"))
    )
    (net (code "67") (name "unconnected-(J105-Pad11)") (class "Default")
      (node (ref "J105") (pin "11") (pinfunction "11_11") (pintype "passive"))
    )
    (net (code "68") (name "unconnected-(J105-Pad12)") (class "Default")
      (node (ref "J105") (pin "12") (pinfunction "12_12") (pintype "passive"))
    )
    (net (code "69") (name "unconnected-(U102-EN1-Pad7)") (class "Default")
      (node (ref "U102") (pin "7") (pinfunction "EN1_7") (pintype "input+no_connect"))
    )
    (net (code "70") (name "unconnected-(U102-EN2-Pad10)") (class "Default")
      (node (ref "U102") (pin "10") (pinfunction "EN2_10") (pintype "input+no_connect"))
    )
    (net (code "71") (name "unconnected-(U102-NC-Pad6)") (class "Default")
      (node (ref "U102") (pin "6") (pinfunction "NC_6") (pintype "passive+no_connect"))
    )
    (net (code "72") (name "unconnected-(U102-NC-Pad11)") (class "Default")
      (node (ref "U102") (pin "11") (pinfunction "NC_11") (pintype "passive+no_connect"))
    )
  )
)
